# POWER.net
KiCad netlist of a schematic drawn in Altium Designer
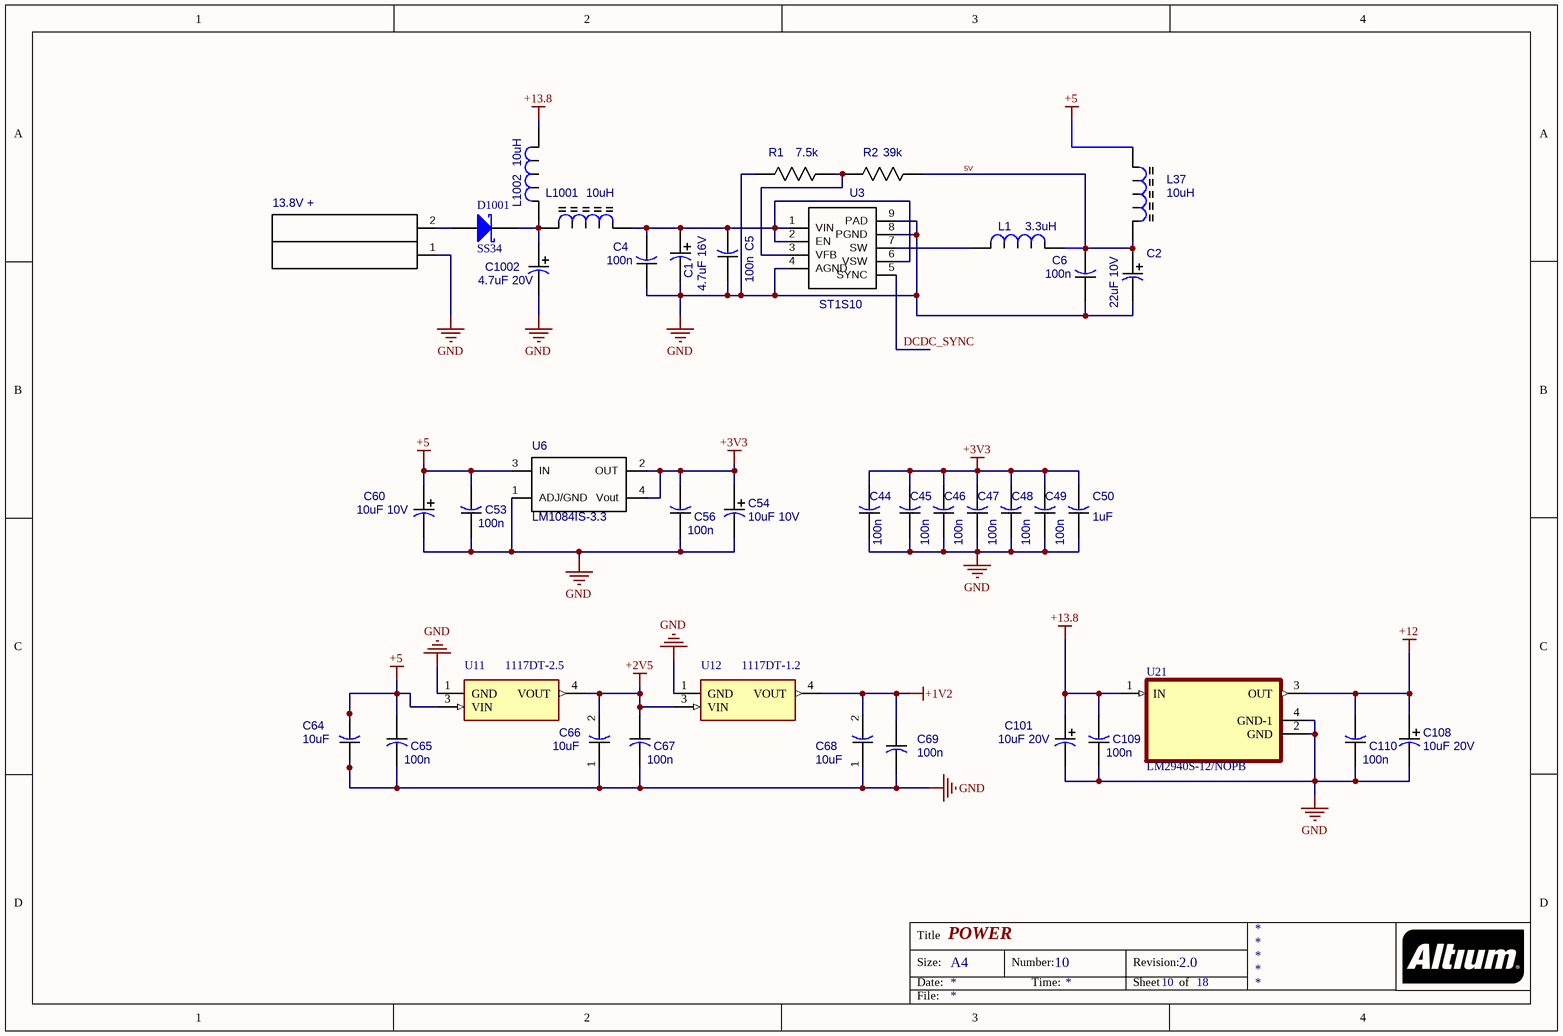
[diagram p0: POWER.SchDoc]

(export (version "E")
  (design (tool "Eeschema 10.0.6"))
  (components
    (comp (ref "13.8V +") (value "JX2") (footprint "JX2") (libsource (lib "*") (part "JX2")))
    (comp (ref "C1")
      (value "4.7uF 16V")
      (footprint "TANTAL_B")
      (description "CAPAE_6.6x6.6h5.4")
      (libsource (lib "*") (part "CAPAE_6.6x6.6h5.4"))
    )
    (comp (ref "C2")
      (value "22uF 10V")
      (footprint "CAPAE_4.3x4.3h5.4")
      (description "CAPAE_4.3x4.3h5.4")
      (libsource (lib "*") (part "CAPAE_4.3x4.3h5.4"))
    )
    (comp (ref "C4")
      (value "100n")
      (footprint "CAP_0805")
      (description "CAP_0805")
      (libsource (lib "*") (part "CAP_0805"))
    )
    (comp (ref "C5")
      (value "100n")
      (footprint "CAP_0805")
      (description "CAP_0805")
      (libsource (lib "*") (part "CAP_0805"))
    )
    (comp (ref "C6")
      (value "100n")
      (footprint "CAP_0805")
      (description "CAP_0805")
      (libsource (lib "*") (part "CAP_0805"))
    )
    (comp (ref "C44")
      (value "100n")
      (footprint "CAP_0805")
      (description "CAP_0805")
      (libsource (lib "*") (part "CAP_0805"))
    )
    (comp (ref "C45")
      (value "100n")
      (footprint "CAP_0805")
      (description "CAP_0805")
      (libsource (lib "*") (part "CAP_0805"))
    )
    (comp (ref "C46")
      (value "100n")
      (footprint "CAP_0805")
      (description "CAP_0805")
      (libsource (lib "*") (part "CAP_0805"))
    )
    (comp (ref "C47")
      (value "100n")
      (footprint "CAP_0805")
      (description "CAP_0805")
      (libsource (lib "*") (part "CAP_0805"))
    )
    (comp (ref "C48")
      (value "100n")
      (footprint "CAP_0805")
      (description "CAP_0805")
      (libsource (lib "*") (part "CAP_0805"))
    )
    (comp (ref "C49")
      (value "100n")
      (footprint "CAP_0805")
      (description "CAP_0805")
      (libsource (lib "*") (part "CAP_0805"))
    )
    (comp (ref "C50")
      (value "1uF")
      (footprint "CAP_0805")
      (description "CAP_0805")
      (fields (field (name "Comment") "10uF"))
      (libsource (lib "*") (part "CAP_0805"))
    )
    (comp (ref "C53")
      (value "100n")
      (footprint "CAP_0805")
      (description "CAP_0805")
      (libsource (lib "*") (part "CAP_0805"))
    )
    (comp (ref "C54")
      (value "10uF 10V")
      (footprint "CAPAE_4.3x4.3h5.4")
      (description "CAPAE_4.3x4.3h5.4")
      (libsource (lib "*") (part "CAPAE_4.3x4.3h5.4"))
    )
    (comp (ref "C56")
      (value "100n")
      (footprint "CAP_0805")
      (description "CAP_0805")
      (libsource (lib "*") (part "CAP_0805"))
    )
    (comp (ref "C60")
      (value "10uF 10V")
      (footprint "CAPAE_4.3x4.3h5.4")
      (description "CAPAE_4.3x4.3h5.4")
      (libsource (lib "*") (part "CAPAE_4.3x4.3h5.4"))
    )
    (comp (ref "C64")
      (value "10uF")
      (footprint "CAP_0805")
      (description "CAP_0805")
      (libsource (lib "") (part "CAP_0805_1"))
    )
    (comp (ref "C65")
      (value "100n")
      (footprint "CAP_0805")
      (description "CAP_0805")
      (libsource (lib "*") (part "CAP_0805"))
    )
    (comp (ref "C66")
      (value "10uF")
      (footprint "CAP_0805")
      (description "CAP_0805")
      (libsource (lib "MOTHERBOARD") (part "CAP_0805"))
    )
    (comp (ref "C67")
      (value "100n")
      (footprint "CAP_0805")
      (description "CAP_0805")
      (libsource (lib "*") (part "CAP_0805"))
    )
    (comp (ref "C68")
      (value "10uF")
      (footprint "CAP_0805")
      (description "CAP_0805")
      (libsource (lib "MOTHERBOARD") (part "CAP_0805"))
    )
    (comp (ref "C69")
      (value "100n")
      (footprint "CAP_0805")
      (description "CAP_0805")
      (libsource (lib "*") (part "CAP_0805"))
    )
    (comp (ref "C101")
      (value "10uF 20V")
      (footprint "CAPAE_4.3x4.3h5.4")
      (description "CAPAE_4.3x4.3h5.4")
      (libsource (lib "*") (part "CAPAE_4.3x4.3h5.4"))
    )
    (comp (ref "C108")
      (value "10uF 20V")
      (footprint "CAPAE_4.3x4.3h5.4")
      (description "CAPAE_4.3x4.3h5.4")
      (libsource (lib "*") (part "CAPAE_4.3x4.3h5.4"))
    )
    (comp (ref "C109")
      (value "100n")
      (footprint "CAP_0805")
      (description "CAP_0805")
      (libsource (lib "*") (part "CAP_0805"))
    )
    (comp (ref "C110")
      (value "100n")
      (footprint "CAP_0805")
      (description "CAP_0805")
      (libsource (lib "*") (part "CAP_0805"))
    )
    (comp (ref "C1002")
      (value "4.7uF 20V")
      (footprint "CAPAE_4.3x4.3h5.4")
      (description "CAPAE_4.3x4.3h5.4")
      (fields (field (name "Comment") "10uF 10V"))
      (libsource (lib "*") (part "CAPAE_4.3x4.3h5.4"))
    )
    (comp (ref "D1001")
      (value "SS34")
      (footprint "SMB")
      (description "Schottky Diode")
      (fields (field (name "PUBLISHER") "Altium Limited"))
      (libsource (lib "Miscellaneous Devices") (part "D Schottky"))
    )
    (comp (ref "L1")
      (value "3.3uH")
      (footprint "IND_1812")
      (description "IND_1812")
      (libsource (lib "*") (part "IND_1812"))
    )
    (comp (ref "L37")
      (value "10uH")
      (footprint "IND_7x7")
      (description "Inductor")
      (libsource (lib "MOTHERBOARD_1") (part "IND_FERRITE_CORE"))
    )
    (comp (ref "L1001")
      (value "10uH")
      (footprint "IND_7x7")
      (description "Inductor")
      (libsource (lib "MOTHERBOARD_1") (part "IND_FERRITE_CORE"))
    )
    (comp (ref "L1002")
      (value "10uH")
      (footprint "IND_1812")
      (description "IND_1812")
      (libsource (lib "*") (part "IND_1812"))
    )
    (comp (ref "R1")
      (value "7.5k")
      (footprint "RES_0805")
      (description "RES_0805")
      (libsource (lib "*") (part "RES_0805"))
    )
    (comp (ref "R2")
      (value "39k")
      (footprint "RES_0805")
      (description "RES_0805")
      (libsource (lib "*") (part "RES_0805"))
    )
    (comp (ref "U3") (value "ST1S10") (footprint "ST1S10") (libsource (lib "*") (part "ST1S10")))
    (comp (ref "U6")
      (value "LM1084IS-3.3")
      (footprint "LM1085-3.3")
      (libsource (lib "*") (part "LM1085-3.3"))
    )
    (comp (ref "U11")
      (value "1117DT-2.5")
      (footprint "SamacSys:TO228P991X238-3N")
      (description "LD1117DT-2.5 DPAK")
      (fields
        (field (name "MANUFACTURER_PART_NUMBER") "LM1117DT-ADJ")
        (field (name "MOUSER PART NUMBER") "926-LM1117DT-ADJ")
      )
      (libsource (lib "*") (part "LM1117DT-ADJ"))
    )
    (comp (ref "U12")
      (value "1117DT-1.2")
      (footprint "SamacSys:TO228P991X238-3N")
      (description "LD1117DT-1.2 DPAK")
      (fields
        (field (name "MANUFACTURER_PART_NUMBER") "LM1117DT-ADJ")
        (field (name "MOUSER PART NUMBER") "926-LM1117DT-ADJ")
      )
      (libsource (lib "*") (part "LM1117DT-ADJ"))
    )
    (comp (ref "U21")
      (value "LM2940S-12/NOPB")
      (footprint "TO254P1524X483-4N")
      (description "1-A, 26-V, high-PSRR, low-dropout voltage regulator")
      (fields (field (name "MF") "Texas Instruments"))
      (libsource (lib "LM2940S-12_NOPB") (part "LM2940S-12/NOPB"))
    )
  )
  (nets
    (net (code "1") (name "+1V2") (class "Default")
      (node (ref "C68") (pin "2") (pinfunction "2_2") (pintype "passive"))
      (node (ref "C69") (pin "1") (pinfunction "1_1") (pintype "passive"))
      (node (ref "U12") (pin "4") (pinfunction "VOUT_4") (pintype "output"))
    )
    (net (code "2") (name "+2V5") (class "Default")
      (node (ref "C66") (pin "2") (pinfunction "2_2") (pintype "passive"))
      (node (ref "C67") (pin "1") (pinfunction "1_1") (pintype "passive"))
      (node (ref "U11") (pin "4") (pinfunction "VOUT_4") (pintype "output"))
      (node (ref "U12") (pin "3") (pinfunction "VIN_3") (pintype "input"))
    )
    (net (code "3") (name "+3V3") (class "Default")
      (node (ref "C44") (pin "2") (pinfunction "2_2") (pintype "passive"))
      (node (ref "C45") (pin "2") (pinfunction "2_2") (pintype "passive"))
      (node (ref "C46") (pin "2") (pinfunction "2_2") (pintype "passive"))
      (node (ref "C47") (pin "2") (pinfunction "2_2") (pintype "passive"))
      (node (ref "C48") (pin "2") (pinfunction "2_2") (pintype "passive"))
      (node (ref "C49") (pin "2") (pinfunction "2_2") (pintype "passive"))
      (node (ref "C50") (pin "2") (pinfunction "2_2") (pintype "passive"))
      (node (ref "C54") (pin "1") (pinfunction "PLUS_1") (pintype "passive"))
      (node (ref "C56") (pin "2") (pinfunction "2_2") (pintype "passive"))
      (node (ref "U6") (pin "2") (pinfunction "OUT_2") (pintype "passive"))
      (node (ref "U6") (pin "4") (pinfunction "Vout_4") (pintype "passive"))
    )
    (net (code "4") (name "+5") (class "Default")
      (node (ref "C53") (pin "2") (pinfunction "2_2") (pintype "passive"))
      (node (ref "C60") (pin "1") (pinfunction "PLUS_1") (pintype "passive"))
      (node (ref "C64") (pin "2") (pinfunction "2_2") (pintype "passive"))
      (node (ref "C65") (pin "1") (pinfunction "1_1") (pintype "passive"))
      (node (ref "L37") (pin "1") (pinfunction "A_1") (pintype "passive"))
      (node (ref "U11") (pin "3") (pinfunction "VIN_3") (pintype "input"))
      (node (ref "U6") (pin "3") (pinfunction "IN_3") (pintype "passive"))
    )
    (net (code "5") (name "+12") (class "Default")
      (node (ref "C108") (pin "1") (pinfunction "PLUS_1") (pintype "passive"))
      (node (ref "C110") (pin "2") (pinfunction "2_2") (pintype "passive"))
      (node (ref "U21") (pin "3") (pinfunction "OUT_3") (pintype "output"))
    )
    (net (code "6") (name "+13.8") (class "Default")
      (node (ref "C101") (pin "1") (pinfunction "PLUS_1") (pintype "passive"))
      (node (ref "C109") (pin "2") (pinfunction "2_2") (pintype "passive"))
      (node (ref "L1002") (pin "2") (pinfunction "2_2") (pintype "passive"))
      (node (ref "U21") (pin "1") (pinfunction "IN_1") (pintype "input"))
    )
    (net (code "7") (name "/5V") (class "Default")
      (node (ref "C2") (pin "1") (pinfunction "PLUS_1") (pintype "passive"))
      (node (ref "C6") (pin "2") (pinfunction "2_2") (pintype "passive"))
      (node (ref "L1") (pin "2") (pinfunction "2_2") (pintype "passive"))
      (node (ref "L37") (pin "2") (pinfunction "B_2") (pintype "passive"))
      (node (ref "R2") (pin "2") (pinfunction "2_2") (pintype "passive"))
    )
    (net (code "8") (name "/DCDC_SYNC") (class "Default")
      (node (ref "U3") (pin "5") (pinfunction "SYNC_5") (pintype "passive"))
    )
    (net (code "9") (name "GND") (class "Default")
      (node (ref "13.8V +") (pin "1") (pinfunction "2_1") (pintype "passive"))
      (node (ref "C1") (pin "2") (pinfunction "MINUS_2") (pintype "passive"))
      (node (ref "C1002") (pin "2") (pinfunction "MINUS_2") (pintype "passive"))
      (node (ref "C101") (pin "2") (pinfunction "MINUS_2") (pintype "passive"))
      (node (ref "C108") (pin "2") (pinfunction "MINUS_2") (pintype "passive"))
      (node (ref "C109") (pin "1") (pinfunction "1_1") (pintype "passive"))
      (node (ref "C110") (pin "1") (pinfunction "1_1") (pintype "passive"))
      (node (ref "C2") (pin "2") (pinfunction "MINUS_2") (pintype "passive"))
      (node (ref "C4") (pin "1") (pinfunction "1_1") (pintype "passive"))
      (node (ref "C44") (pin "1") (pinfunction "1_1") (pintype "passive"))
      (node (ref "C45") (pin "1") (pinfunction "1_1") (pintype "passive"))
      (node (ref "C46") (pin "1") (pinfunction "1_1") (pintype "passive"))
      (node (ref "C47") (pin "1") (pinfunction "1_1") (pintype "passive"))
      (node (ref "C48") (pin "1") (pinfunction "1_1") (pintype "passive"))
      (node (ref "C49") (pin "1") (pinfunction "1_1") (pintype "passive"))
      (node (ref "C5") (pin "1") (pinfunction "1_1") (pintype "passive"))
      (node (ref "C50") (pin "1") (pinfunction "1_1") (pintype "passive"))
      (node (ref "C53") (pin "1") (pinfunction "1_1") (pintype "passive"))
      (node (ref "C54") (pin "2") (pinfunction "MINUS_2") (pintype "passive"))
      (node (ref "C56") (pin "1") (pinfunction "1_1") (pintype "passive"))
      (node (ref "C6") (pin "1") (pinfunction "1_1") (pintype "passive"))
      (node (ref "C60") (pin "2") (pinfunction "MINUS_2") (pintype "passive"))
      (node (ref "C64") (pin "1") (pinfunction "1_1") (pintype "passive"))
      (node (ref "C65") (pin "2") (pinfunction "2_2") (pintype "passive"))
      (node (ref "C66") (pin "1") (pinfunction "1_1") (pintype "passive"))
      (node (ref "C67") (pin "2") (pinfunction "2_2") (pintype "passive"))
      (node (ref "C68") (pin "1") (pinfunction "1_1") (pintype "passive"))
      (node (ref "C69") (pin "2") (pinfunction "2_2") (pintype "passive"))
      (node (ref "R1") (pin "1") (pinfunction "1_1") (pintype "passive"))
      (node (ref "U11") (pin "1") (pinfunction "GND_1") (pintype "passive"))
      (node (ref "U12") (pin "1") (pinfunction "GND_1") (pintype "passive"))
      (node (ref "U21") (pin "2") (pinfunction "GND_2") (pintype "power_in"))
      (node (ref "U21") (pin "4") (pinfunction "GND-1_4") (pintype "power_in"))
      (node (ref "U3") (pin "4") (pinfunction "AGND_4") (pintype "passive"))
      (node (ref "U3") (pin "8") (pinfunction "PGND_8") (pintype "passive"))
      (node (ref "U3") (pin "9") (pinfunction "PAD_9") (pintype "passive"))
      (node (ref "U6") (pin "1") (pinfunction "ADJ/GND_1") (pintype "passive"))
    )
    (net (code "10") (name "Net-(13.8V +-1)") (class "Default")
      (node (ref "13.8V +") (pin "2") (pinfunction "1_2") (pintype "passive"))
      (node (ref "D1001") (pin "1") (pinfunction "A_1") (pintype "passive"))
    )
    (net (code "11") (name "Net-(C1-PLUS)") (class "Default")
      (node (ref "C1") (pin "1") (pinfunction "PLUS_1") (pintype "passive"))
      (node (ref "C4") (pin "2") (pinfunction "2_2") (pintype "passive"))
      (node (ref "C5") (pin "2") (pinfunction "2_2") (pintype "passive"))
      (node (ref "L1001") (pin "2") (pinfunction "B_2") (pintype "passive"))
      (node (ref "U3") (pin "1") (pinfunction "VIN_1") (pintype "passive"))
      (node (ref "U3") (pin "2") (pinfunction "EN_2") (pintype "passive"))
      (node (ref "U3") (pin "6") (pinfunction "VSW_6") (pintype "passive"))
    )
    (net (code "12") (name "Net-(C1002-PLUS)") (class "Default")
      (node (ref "C1002") (pin "1") (pinfunction "PLUS_1") (pintype "passive"))
      (node (ref "D1001") (pin "2") (pinfunction "K_2") (pintype "passive"))
      (node (ref "L1001") (pin "1") (pinfunction "A_1") (pintype "passive"))
      (node (ref "L1002") (pin "1") (pinfunction "1_1") (pintype "passive"))
    )
    (net (code "13") (name "Net-(U3-SW)") (class "Default")
      (node (ref "L1") (pin "1") (pinfunction "1_1") (pintype "passive"))
      (node (ref "U3") (pin "7") (pinfunction "SW_7") (pintype "passive"))
    )
    (net (code "14") (name "Net-(U3-VFB)") (class "Default")
      (node (ref "R1") (pin "2") (pinfunction "2_2") (pintype "passive"))
      (node (ref "R2") (pin "1") (pinfunction "1_1") (pintype "passive"))
      (node (ref "U3") (pin "3") (pinfunction "VFB_3") (pintype "passive"))
    )
  )
)
